# MPU6050.net
KiCad netlist of a schematic drawn in Altium Designer
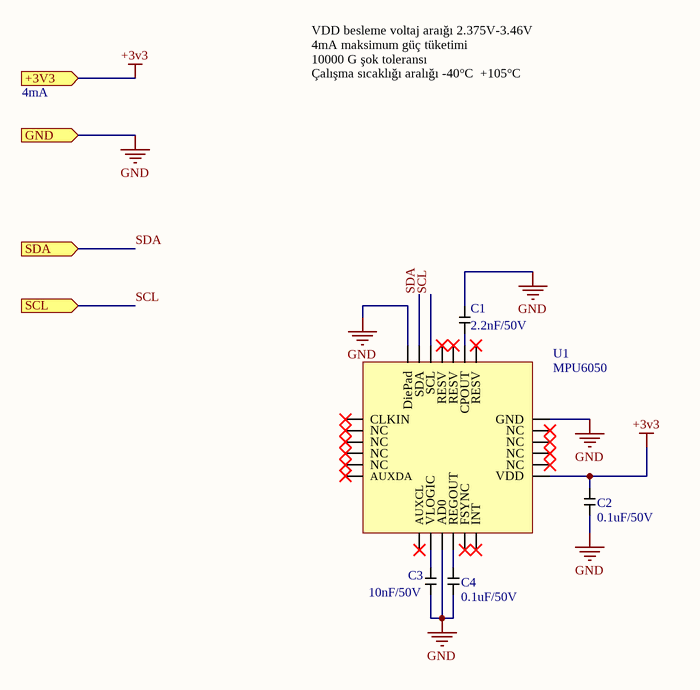
[diagram p0: MPU6050.SchDoc]

(export (version "E")
  (design (tool "Eeschema 10.0.6"))
  (components
    (comp (ref "C1")
      (value "2.2nF/50V")
      (description "MLCC (2012) 0805 2.2nF 50VDC ±10% X7R")
      (libsource (lib "Roket_Library") (part "CL21B222KBANNNC"))
    )
    (comp (ref "C2")
      (value "0.1uF/50V")
      (footprint "Cap_0805")
      (description "MLCC (2012) 0805 100nF 50VDC ±5% X7R")
      (libsource (lib "Roket_Library") (part "CL21B104JBCNNNC"))
    )
    (comp (ref "C3")
      (value "10nF/50V")
      (footprint "Cap_0805")
      (description "MLCC (2012) 0805 10nF 50VDC ±10% X7R")
      (libsource (lib "Roket_Library") (part "CL21B103KBANNNC"))
    )
    (comp (ref "C4")
      (value "0.1uF/50V")
      (footprint "Cap_0805")
      (description "MLCC (2012) 0805 100nF 50VDC ±5% X7R")
      (libsource (lib "Roket_Library") (part "CL21B104JBCNNNC"))
    )
    (comp (ref "U1")
      (value "MPU6050")
      (footprint "QFN24")
      (description "IC-6050 SENSOR MOTION QFN24")
      (libsource (lib "Roket_Library") (part "MPU-6050"))
    )
  )
  (nets
    (net (code "1") (name "+3v3") (class "Default")
      (node (ref "C2") (pin "1") (pinfunction "1_1") (pintype "passive"))
      (node (ref "U1") (pin "13") (pinfunction "VDD_13") (pintype "passive"))
    )
    (net (code "2") (name "/SCL") (class "Default")
      (node (ref "U1") (pin "23") (pinfunction "SCL_23") (pintype "passive"))
    )
    (net (code "3") (name "/SDA") (class "Default")
      (node (ref "U1") (pin "24") (pinfunction "SDA_24") (pintype "passive"))
    )
    (net (code "4") (name "GND") (class "Default")
      (node (ref "C1") (pin "1") (pinfunction "2_1") (pintype "passive"))
      (node (ref "C2") (pin "2") (pinfunction "2_2") (pintype "passive"))
      (node (ref "C3") (pin "1") (pinfunction "1_1") (pintype "passive"))
      (node (ref "C4") (pin "2") (pinfunction "2_2") (pintype "passive"))
      (node (ref "U1") (pin "18") (pinfunction "GND_18") (pintype "passive"))
      (node (ref "U1") (pin "25") (pinfunction "DiePad_25") (pintype "passive"))
      (node (ref "U1") (pin "9") (pinfunction "AD0_9") (pintype "passive"))
    )
    (net (code "5") (name "Net-(C1-2)") (class "Default")
      (node (ref "C1") (pin "1") (pinfunction "2_1") (pintype "passive"))
      (node (ref "U1") (pin "20") (pinfunction "CPOUT_20") (pintype "passive"))
    )
    (net (code "6") (name "Net-(U1-REGOUT)") (class "Default")
      (node (ref "C4") (pin "1") (pinfunction "1_1") (pintype "passive"))
      (node (ref "U1") (pin "10") (pinfunction "REGOUT_10") (pintype "passive"))
    )
    (net (code "7") (name "Net-(U1-VLOGIC)") (class "Default")
      (node (ref "C3") (pin "2") (pinfunction "2_2") (pintype "passive"))
      (node (ref "U1") (pin "8") (pinfunction "VLOGIC_8") (pintype "passive"))
    )
    (net (code "8") (name "unconnected-(U1-AUXCL-Pad7)") (class "Default")
      (node (ref "U1") (pin "7") (pinfunction "AUXCL_7") (pintype "passive+no_connect"))
    )
    (net (code "9") (name "unconnected-(U1-AUXDA-Pad6)") (class "Default")
      (node (ref "U1") (pin "6") (pinfunction "AUXDA_6") (pintype "passive+no_connect"))
    )
    (net (code "10") (name "unconnected-(U1-CLKIN-Pad1)") (class "Default")
      (node (ref "U1") (pin "1") (pinfunction "CLKIN_1") (pintype "passive+no_connect"))
    )
    (net (code "11") (name "unconnected-(U1-FSYNC-Pad11)") (class "Default")
      (node (ref "U1") (pin "11") (pinfunction "FSYNC_11") (pintype "passive+no_connect"))
    )
    (net (code "12") (name "unconnected-(U1-INT-Pad12)") (class "Default")
      (node (ref "U1") (pin "12") (pinfunction "INT_12") (pintype "passive+no_connect"))
    )
    (net (code "13") (name "unconnected-(U1-NC-Pad2)") (class "Default")
      (node (ref "U1") (pin "2") (pinfunction "NC_2") (pintype "passive+no_connect"))
    )
    (net (code "14") (name "unconnected-(U1-NC-Pad3)") (class "Default")
      (node (ref "U1") (pin "3") (pinfunction "NC_3") (pintype "passive+no_connect"))
    )
    (net (code "15") (name "unconnected-(U1-NC-Pad4)") (class "Default")
      (node (ref "U1") (pin "4") (pinfunction "NC_4") (pintype "passive+no_connect"))
    )
    (net (code "16") (name "unconnected-(U1-NC-Pad5)") (class "Default")
      (node (ref "U1") (pin "5") (pinfunction "NC_5") (pintype "passive+no_connect"))
    )
    (net (code "17") (name "unconnected-(U1-NC-Pad14)") (class "Default")
      (node (ref "U1") (pin "14") (pinfunction "NC_14") (pintype "passive+no_connect"))
    )
    (net (code "18") (name "unconnected-(U1-NC-Pad15)") (class "Default")
      (node (ref "U1") (pin "15") (pinfunction "NC_15") (pintype "passive+no_connect"))
    )
    (net (code "19") (name "unconnected-(U1-NC-Pad16)") (class "Default")
      (node (ref "U1") (pin "16") (pinfunction "NC_16") (pintype "passive+no_connect"))
    )
    (net (code "20") (name "unconnected-(U1-NC-Pad17)") (class "Default")
      (node (ref "U1") (pin "17") (pinfunction "NC_17") (pintype "passive+no_connect"))
    )
    (net (code "21") (name "unconnected-(U1-RESV-Pad19)") (class "Default")
      (node (ref "U1") (pin "19") (pinfunction "RESV_19") (pintype "passive+no_connect"))
    )
    (net (code "22") (name "unconnected-(U1-RESV-Pad21)") (class "Default")
      (node (ref "U1") (pin "21") (pinfunction "RESV_21") (pintype "passive+no_connect"))
    )
    (net (code "23") (name "unconnected-(U1-RESV-Pad22)") (class "Default")
      (node (ref "U1") (pin "22") (pinfunction "RESV_22") (pintype "passive+no_connect"))
    )
  )
)
